# CH3_CH4.net
KiCad netlist of a schematic drawn in Altium Designer
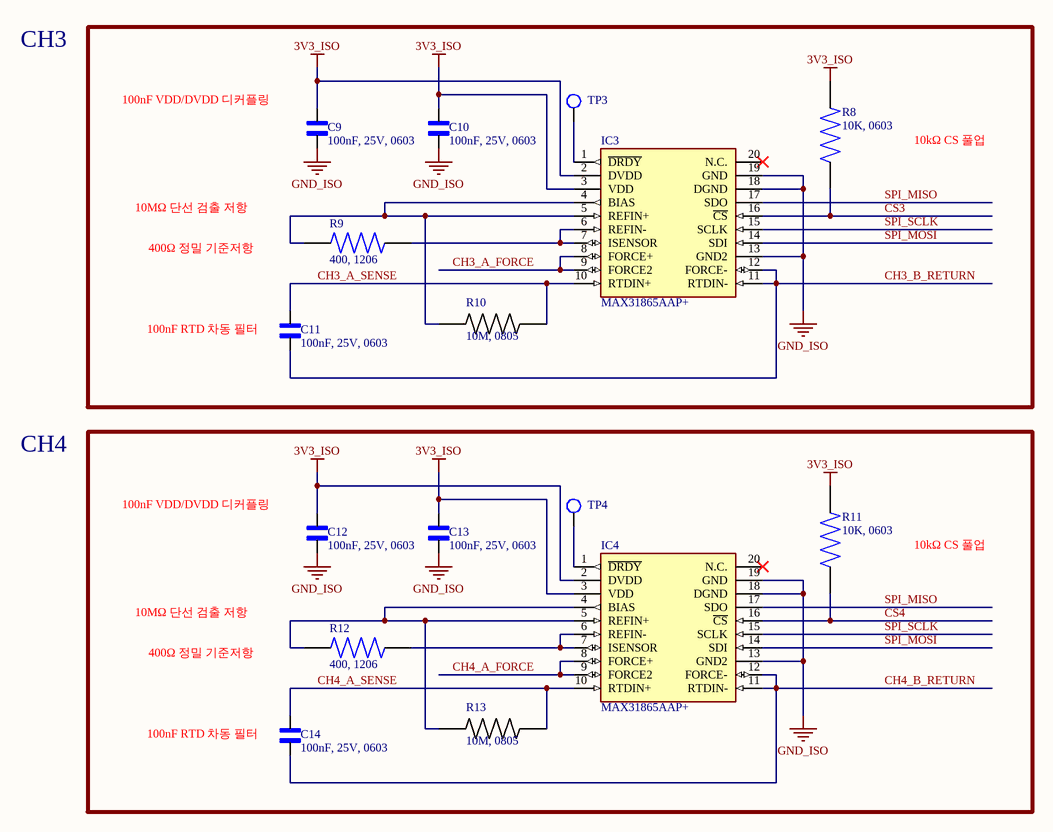
[diagram p0: CH3_CH4.SchDoc]

(export (version "E")
  (design (tool "Eeschema 10.0.6"))
  (components
    (comp (ref "C9")
      (value "100nF, 25V, 0603")
      (footprint "CAPC1608X90N")
      (description "Multilayer Ceramic Capacitors MLCC - SMD/SMT")
      (fields (field (name "MF") "Samsung Electro-Mechanics") (field (name "MP") "CL10B104KA8VPJC"))
      (libsource (lib "CL10B104KA8VPJC") (part "CL10B104KA8VPJC"))
    )
    (comp (ref "C10")
      (value "100nF, 25V, 0603")
      (footprint "CAPC1608X90N")
      (description "Multilayer Ceramic Capacitors MLCC - SMD/SMT")
      (fields (field (name "MF") "Samsung Electro-Mechanics") (field (name "MP") "CL10B104KA8VPJC"))
      (libsource (lib "CL10B104KA8VPJC") (part "CL10B104KA8VPJC"))
    )
    (comp (ref "C11")
      (value "100nF, 25V, 0603")
      (footprint "CAPC1608X90N")
      (description "Multilayer Ceramic Capacitors MLCC - SMD/SMT")
      (fields (field (name "MF") "Samsung Electro-Mechanics") (field (name "MP") "CL10B104KA8VPJC"))
      (libsource (lib "CL10B104KA8VPJC") (part "CL10B104KA8VPJC"))
    )
    (comp (ref "C12")
      (value "100nF, 25V, 0603")
      (footprint "CAPC1608X90N")
      (description "Multilayer Ceramic Capacitors MLCC - SMD/SMT")
      (fields (field (name "MF") "Samsung Electro-Mechanics") (field (name "MP") "CL10B104KA8VPJC"))
      (libsource (lib "CL10B104KA8VPJC") (part "CL10B104KA8VPJC"))
    )
    (comp (ref "C13")
      (value "100nF, 25V, 0603")
      (footprint "CAPC1608X90N")
      (description "Multilayer Ceramic Capacitors MLCC - SMD/SMT")
      (fields (field (name "MF") "Samsung Electro-Mechanics") (field (name "MP") "CL10B104KA8VPJC"))
      (libsource (lib "CL10B104KA8VPJC") (part "CL10B104KA8VPJC"))
    )
    (comp (ref "C14")
      (value "100nF, 25V, 0603")
      (footprint "CAPC1608X90N")
      (description "Multilayer Ceramic Capacitors MLCC - SMD/SMT")
      (fields (field (name "MF") "Samsung Electro-Mechanics") (field (name "MP") "CL10B104KA8VPJC"))
      (libsource (lib "CL10B104KA8VPJC") (part "CL10B104KA8VPJC"))
    )
    (comp (ref "IC3")
      (value "MAX31865AAP+")
      (footprint "SamacSys:SOP65P778X199-20N")
      (description "Integrated Circuit")
      (fields (field (name "MOUSER PART NUMBER") "700-MAX31865AAP+"))
      (libsource (lib "MAX31865AAP+") (part "MAX31865AAP+"))
    )
    (comp (ref "IC4")
      (value "MAX31865AAP+")
      (footprint "SamacSys:SOP65P778X199-20N")
      (description "Integrated Circuit")
      (fields (field (name "MOUSER PART NUMBER") "700-MAX31865AAP+"))
      (libsource (lib "MAX31865AAP+") (part "MAX31865AAP+"))
    )
    (comp (ref "R8")
      (value "10K, 0603")
      (footprint "RESC1607X60N")
      (description "10 kOhms ±1% 0.1W, 1/10W Chip Resistor 0603 (1608 Metric) Moisture Resistant Thick Film")
      (fields (field (name "MF") "Yageo Corporation") (field (name "MP") "RC0603FR0710KL"))
      (libsource (lib "RC0603FR-0710KL") (part "RC0603FR-0710KL"))
    )
    (comp (ref "R9")
      (value "400, 1206")
      (footprint "RESC3116X65N")
      (description "400 Ohms Â±0.1% 0.25W, 1/4W Chip Resistor 1206 (3216 Metric) - Thin Film")
      (fields (field (name "MF") "Yageo") (field (name "MP") "RT1206BRD07400RL"))
      (libsource (lib "RT1206BRD07400RL") (part "RT1206BRD07400RL"))
    )
    (comp (ref "R10")
      (value "10M, 0805")
      (footprint "*RESC2012X60N")
      (description "10MΩ, ±1%, 125mW, 0805, AEC-Q200")
      (libsource (lib "AC0805FR-1010ML") (part "AC0805FR-1010ML"))
    )
    (comp (ref "R11")
      (value "10K, 0603")
      (footprint "RESC1607X60N")
      (description "10 kOhms ±1% 0.1W, 1/10W Chip Resistor 0603 (1608 Metric) Moisture Resistant Thick Film")
      (fields (field (name "MF") "Yageo Corporation") (field (name "MP") "RC0603FR0710KL"))
      (libsource (lib "RC0603FR-0710KL") (part "RC0603FR-0710KL"))
    )
    (comp (ref "R12")
      (value "400, 1206")
      (footprint "RESC3116X65N")
      (description "400 Ohms Â±0.1% 0.25W, 1/4W Chip Resistor 1206 (3216 Metric) - Thin Film")
      (fields (field (name "MF") "Yageo") (field (name "MP") "RT1206BRD07400RL"))
      (libsource (lib "RT1206BRD07400RL") (part "RT1206BRD07400RL"))
    )
    (comp (ref "R13")
      (value "10M, 0805")
      (footprint "*RESC2012X60N")
      (description "10MΩ, ±1%, 125mW, 0805, AEC-Q200")
      (libsource (lib "AC0805FR-1010ML") (part "AC0805FR-1010ML"))
    )
    (comp (ref "TP3")
      (value "TEST POINT")
      (footprint "TESTPOINT")
      (libsource (lib "TP1.0-SMD") (part "TEST POINT"))
    )
    (comp (ref "TP4")
      (value "TEST POINT")
      (footprint "TESTPOINT")
      (libsource (lib "TP1.0-SMD") (part "TEST POINT"))
    )
  )
  (nets
    (net (code "1") (name "/CH3_A_FORCE") (class "Default")
      (node (ref "IC3") (pin "8") (pinfunction "FORCE+_8") (pintype "bidirectional"))
      (node (ref "IC3") (pin "9") (pinfunction "FORCE2_9") (pintype "bidirectional"))
    )
    (net (code "2") (name "/CH3_A_SENSE") (class "Default")
      (node (ref "C11") (pin "2") (pinfunction "2_2") (pintype "passive"))
      (node (ref "IC3") (pin "10") (pinfunction "RTDIN+_10") (pintype "input"))
      (node (ref "R10") (pin "2") (pinfunction "2_2") (pintype "passive"))
    )
    (net (code "3") (name "/CH3_B_RETURN") (class "Default")
      (node (ref "C11") (pin "1") (pinfunction "1_1") (pintype "passive"))
      (node (ref "IC3") (pin "11") (pinfunction "RTDIN-_11") (pintype "input"))
      (node (ref "IC3") (pin "12") (pinfunction "FORCE-_12") (pintype "bidirectional"))
    )
    (net (code "4") (name "/CH4_A_FORCE") (class "Default")
      (node (ref "IC4") (pin "8") (pinfunction "FORCE+_8") (pintype "bidirectional"))
      (node (ref "IC4") (pin "9") (pinfunction "FORCE2_9") (pintype "bidirectional"))
    )
    (net (code "5") (name "/CH4_A_SENSE") (class "Default")
      (node (ref "C14") (pin "2") (pinfunction "2_2") (pintype "passive"))
      (node (ref "IC4") (pin "10") (pinfunction "RTDIN+_10") (pintype "input"))
      (node (ref "R13") (pin "2") (pinfunction "2_2") (pintype "passive"))
    )
    (net (code "6") (name "/CH4_B_RETURN") (class "Default")
      (node (ref "C14") (pin "1") (pinfunction "1_1") (pintype "passive"))
      (node (ref "IC4") (pin "11") (pinfunction "RTDIN-_11") (pintype "input"))
      (node (ref "IC4") (pin "12") (pinfunction "FORCE-_12") (pintype "bidirectional"))
    )
    (net (code "7") (name "/CS3") (class "Default")
      (node (ref "IC3") (pin "16") (pinfunction "~{CS}_16") (pintype "input"))
      (node (ref "R8") (pin "1") (pinfunction "1_1") (pintype "passive"))
    )
    (net (code "8") (name "/CS4") (class "Default")
      (node (ref "IC4") (pin "16") (pinfunction "~{CS}_16") (pintype "input"))
      (node (ref "R11") (pin "1") (pinfunction "1_1") (pintype "passive"))
    )
    (net (code "9") (name "/SPI_MISO") (class "Default")
      (node (ref "IC3") (pin "17") (pinfunction "SDO_17") (pintype "tri_state"))
      (node (ref "IC4") (pin "17") (pinfunction "SDO_17") (pintype "tri_state"))
    )
    (net (code "10") (name "/SPI_MOSI") (class "Default")
      (node (ref "IC3") (pin "14") (pinfunction "SDI_14") (pintype "input"))
      (node (ref "IC4") (pin "14") (pinfunction "SDI_14") (pintype "input"))
    )
    (net (code "11") (name "/SPI_SCLK") (class "Default")
      (node (ref "IC3") (pin "15") (pinfunction "SCLK_15") (pintype "input"))
      (node (ref "IC4") (pin "15") (pinfunction "SCLK_15") (pintype "input"))
    )
    (net (code "12") (name "3V3_ISO") (class "Default")
      (node (ref "C10") (pin "2") (pinfunction "2_2") (pintype "passive"))
      (node (ref "C12") (pin "2") (pinfunction "2_2") (pintype "passive"))
      (node (ref "C13") (pin "2") (pinfunction "2_2") (pintype "passive"))
      (node (ref "C9") (pin "2") (pinfunction "2_2") (pintype "passive"))
      (node (ref "IC3") (pin "2") (pinfunction "DVDD_2") (pintype "power_in"))
      (node (ref "IC3") (pin "3") (pinfunction "VDD_3") (pintype "power_in"))
      (node (ref "IC4") (pin "2") (pinfunction "DVDD_2") (pintype "power_in"))
      (node (ref "IC4") (pin "3") (pinfunction "VDD_3") (pintype "power_in"))
      (node (ref "R11") (pin "2") (pinfunction "2_2") (pintype "passive"))
      (node (ref "R8") (pin "2") (pinfunction "2_2") (pintype "passive"))
    )
    (net (code "13") (name "GND_ISO") (class "Default")
      (node (ref "C10") (pin "1") (pinfunction "1_1") (pintype "passive"))
      (node (ref "C12") (pin "1") (pinfunction "1_1") (pintype "passive"))
      (node (ref "C13") (pin "1") (pinfunction "1_1") (pintype "passive"))
      (node (ref "C9") (pin "1") (pinfunction "1_1") (pintype "passive"))
      (node (ref "IC3") (pin "13") (pinfunction "GND2_13") (pintype "power_in"))
      (node (ref "IC3") (pin "18") (pinfunction "DGND_18") (pintype "power_in"))
      (node (ref "IC3") (pin "19") (pinfunction "GND_19") (pintype "power_in"))
      (node (ref "IC4") (pin "13") (pinfunction "GND2_13") (pintype "power_in"))
      (node (ref "IC4") (pin "18") (pinfunction "DGND_18") (pintype "power_in"))
      (node (ref "IC4") (pin "19") (pinfunction "GND_19") (pintype "power_in"))
    )
    (net (code "14") (name "Net-(IC3-BIAS)") (class "Default")
      (node (ref "IC3") (pin "4") (pinfunction "BIAS_4") (pintype "output"))
      (node (ref "IC3") (pin "5") (pinfunction "REFIN+_5") (pintype "input"))
      (node (ref "R10") (pin "1") (pinfunction "1_1") (pintype "passive"))
      (node (ref "R9") (pin "1") (pinfunction "1_1") (pintype "passive"))
    )
    (net (code "15") (name "Net-(IC3-ISENSOR)") (class "Default")
      (node (ref "IC3") (pin "6") (pinfunction "REFIN-_6") (pintype "input"))
      (node (ref "IC3") (pin "7") (pinfunction "ISENSOR_7") (pintype "bidirectional"))
      (node (ref "R9") (pin "2") (pinfunction "2_2") (pintype "passive"))
    )
    (net (code "16") (name "Net-(IC3-~{DRDY})") (class "Default")
      (node (ref "IC3") (pin "1") (pinfunction "~{DRDY}_1") (pintype "output"))
      (node (ref "TP3") (pin "1") (pinfunction "1_1") (pintype "passive"))
    )
    (net (code "17") (name "Net-(IC4-BIAS)") (class "Default")
      (node (ref "IC4") (pin "4") (pinfunction "BIAS_4") (pintype "output"))
      (node (ref "IC4") (pin "5") (pinfunction "REFIN+_5") (pintype "input"))
      (node (ref "R12") (pin "1") (pinfunction "1_1") (pintype "passive"))
      (node (ref "R13") (pin "1") (pinfunction "1_1") (pintype "passive"))
    )
    (net (code "18") (name "Net-(IC4-ISENSOR)") (class "Default")
      (node (ref "IC4") (pin "6") (pinfunction "REFIN-_6") (pintype "input"))
      (node (ref "IC4") (pin "7") (pinfunction "ISENSOR_7") (pintype "bidirectional"))
      (node (ref "R12") (pin "2") (pinfunction "2_2") (pintype "passive"))
    )
    (net (code "19") (name "Net-(IC4-~{DRDY})") (class "Default")
      (node (ref "IC4") (pin "1") (pinfunction "~{DRDY}_1") (pintype "output"))
      (node (ref "TP4") (pin "1") (pinfunction "1_1") (pintype "passive"))
    )
    (net (code "20") (name "unconnected-(IC3-N.C.-Pad20)") (class "Default")
      (node (ref "IC3") (pin "20") (pinfunction "N.C._20") (pintype "passive+no_connect"))
    )
    (net (code "21") (name "unconnected-(IC4-N.C.-Pad20)") (class "Default")
      (node (ref "IC4") (pin "20") (pinfunction "N.C._20") (pintype "passive+no_connect"))
    )
  )
)
